# AnalogIn_Teensy_V05.net
KiCad netlist of a schematic drawn in EAGLE
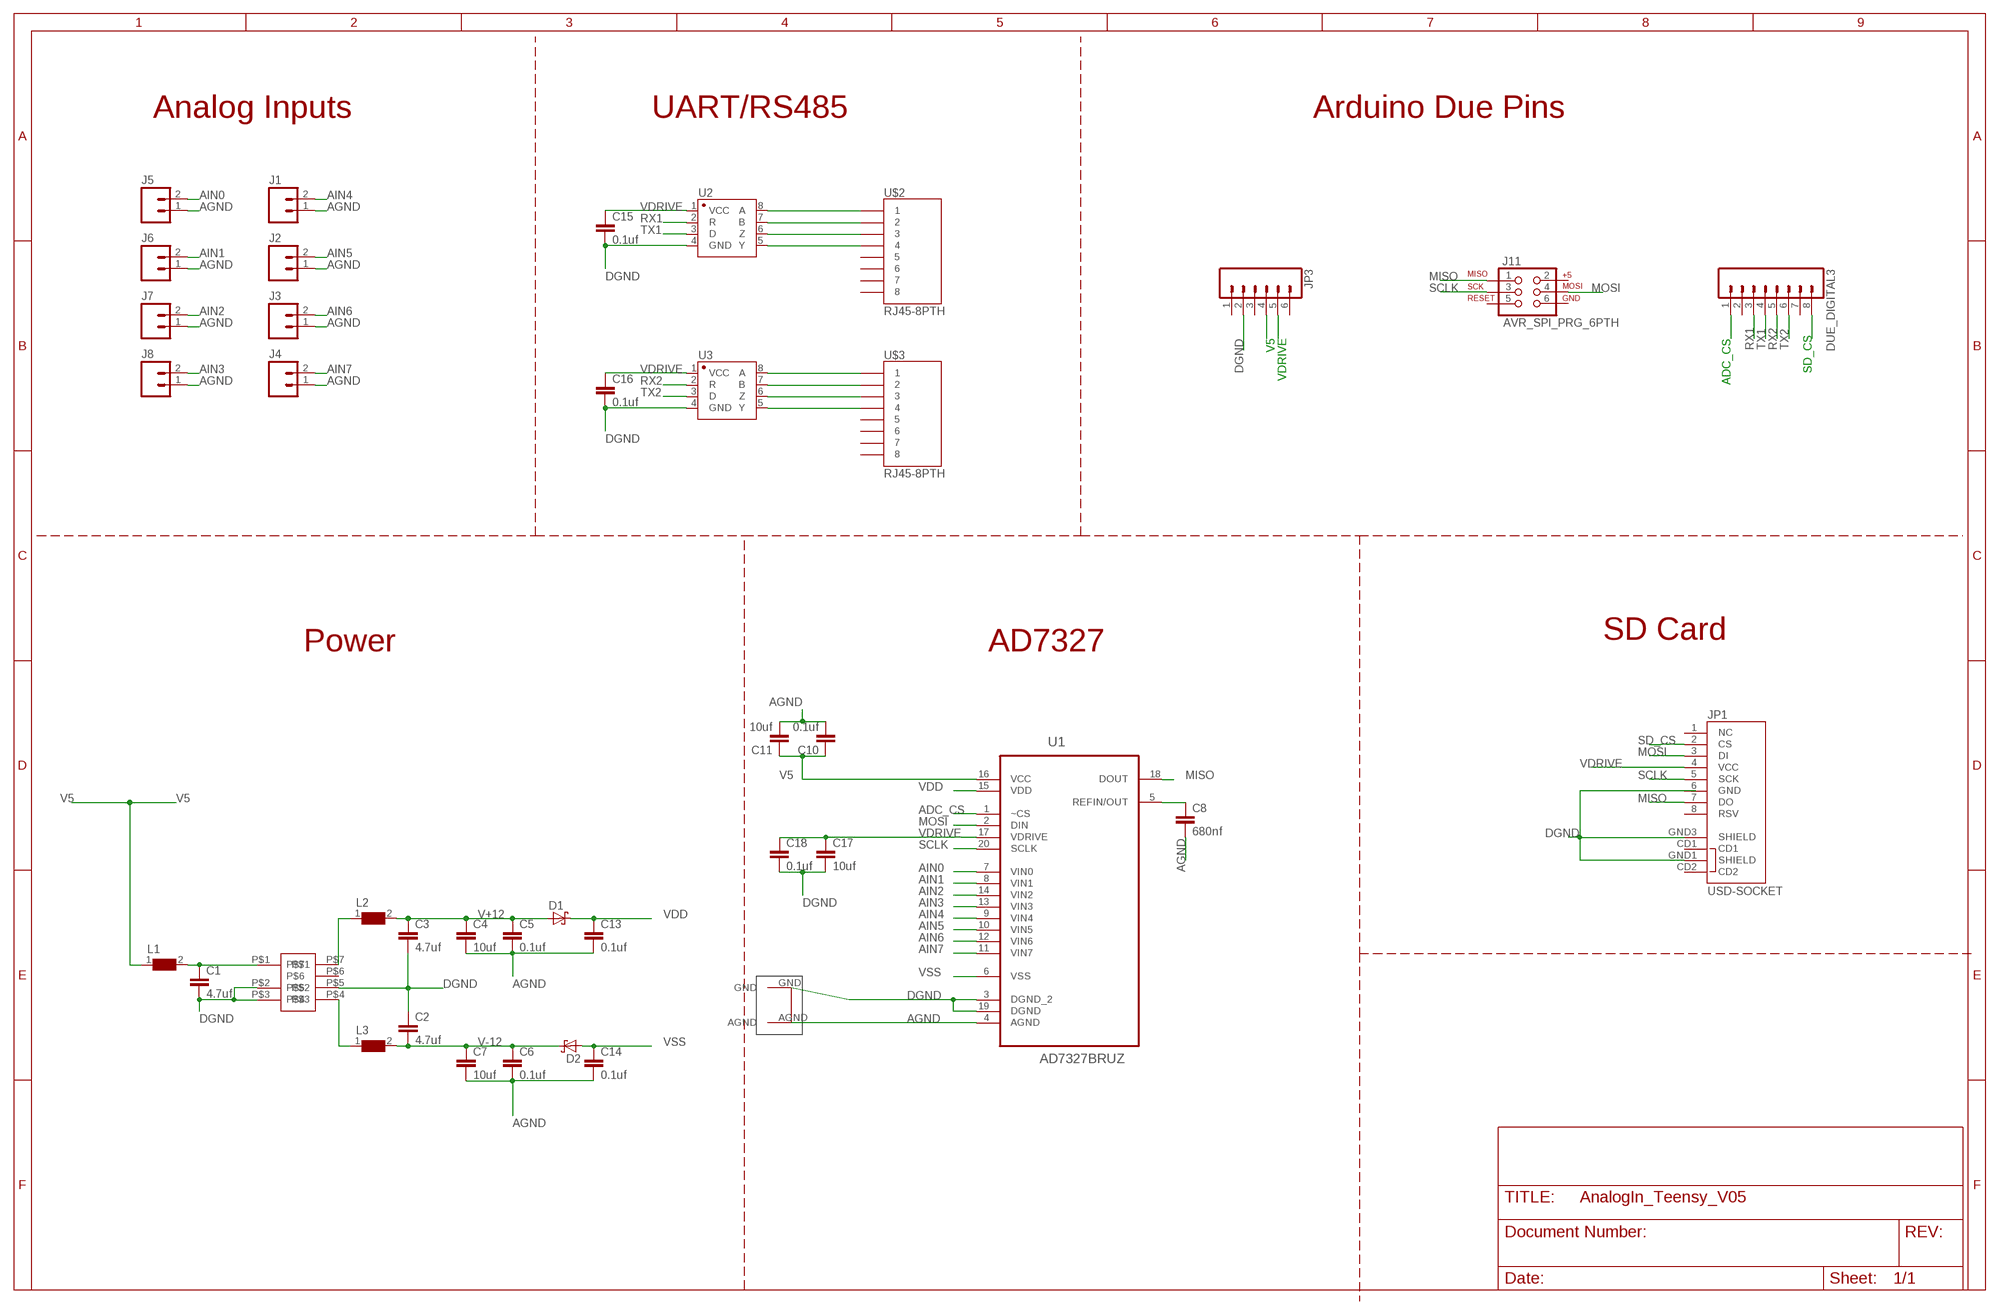
[diagram p0: schematic, sheet 1]

(export (version "E")
  (design (tool "Eeschema 10.0.6"))
  (components
    (comp (ref "C1")
      (value "4.7uf")
      (footprint "eagle-import:1206")
      (libsource (lib "eagle-import") (part "CAP1206"))
    )
    (comp (ref "C2")
      (value "4.7uf")
      (footprint "eagle-import:1206")
      (libsource (lib "eagle-import") (part "CAP1206"))
    )
    (comp (ref "C3")
      (value "4.7uf")
      (footprint "eagle-import:1206")
      (libsource (lib "eagle-import") (part "CAP1206"))
    )
    (comp (ref "C4")
      (value "10uf")
      (footprint "eagle-import:1206")
      (libsource (lib "eagle-import") (part "CAP1206"))
    )
    (comp (ref "C5")
      (value "0.1uf")
      (footprint "eagle-import:1206")
      (libsource (lib "eagle-import") (part "CAP1206"))
    )
    (comp (ref "C6")
      (value "0.1uf")
      (footprint "eagle-import:1206")
      (libsource (lib "eagle-import") (part "CAP1206"))
    )
    (comp (ref "C7")
      (value "10uf")
      (footprint "eagle-import:1206")
      (libsource (lib "eagle-import") (part "CAP1206"))
    )
    (comp (ref "C8")
      (value "680nf")
      (footprint "eagle-import:1206")
      (libsource (lib "eagle-import") (part "CAP1206"))
    )
    (comp (ref "C10")
      (value "0.1uf")
      (footprint "eagle-import:0603-CAP")
      (libsource (lib "eagle-import") (part "CAP0603-CAP"))
    )
    (comp (ref "C11")
      (value "10uf")
      (footprint "eagle-import:0603-CAP")
      (libsource (lib "eagle-import") (part "CAP0603-CAP"))
    )
    (comp (ref "C13")
      (value "0.1uf")
      (footprint "eagle-import:1206")
      (libsource (lib "eagle-import") (part "CAP1206"))
    )
    (comp (ref "C14")
      (value "0.1uf")
      (footprint "eagle-import:1206")
      (libsource (lib "eagle-import") (part "CAP1206"))
    )
    (comp (ref "C15")
      (value "0.1uf")
      (footprint "eagle-import:0603-CAP")
      (libsource (lib "eagle-import") (part "CAP0603-CAP"))
    )
    (comp (ref "C16")
      (value "0.1uf")
      (footprint "eagle-import:0603-CAP")
      (libsource (lib "eagle-import") (part "CAP0603-CAP"))
    )
    (comp (ref "C17")
      (value "10uf")
      (footprint "eagle-import:0603-CAP")
      (libsource (lib "eagle-import") (part "CAP0603-CAP"))
    )
    (comp (ref "C18")
      (value "0.1uf")
      (footprint "eagle-import:0603-CAP")
      (libsource (lib "eagle-import") (part "CAP0603-CAP"))
    )
    (comp (ref "D1")
      (value "SCHOTTKY-DIODESMD")
      (footprint "eagle-import:SMB")
      (libsource (lib "eagle-import") (part "SCHOTTKY-DIODESMD"))
    )
    (comp (ref "D2")
      (value "SCHOTTKY-DIODESMD")
      (footprint "eagle-import:SMB")
      (libsource (lib "eagle-import") (part "SCHOTTKY-DIODESMD"))
    )
    (comp (ref "DUE_DIGITAL3")
      (value "M081X08")
      (footprint "eagle-import:1X08")
      (libsource (lib "eagle-import") (part "M081X08"))
    )
    (comp (ref "J1")
      (value "M023.5MM")
      (footprint "eagle-import:SCREWTERMINAL-3.5MM-2")
      (libsource (lib "eagle-import") (part "M023.5MM"))
    )
    (comp (ref "J2")
      (value "M023.5MM")
      (footprint "eagle-import:SCREWTERMINAL-3.5MM-2")
      (libsource (lib "eagle-import") (part "M023.5MM"))
    )
    (comp (ref "J3")
      (value "M023.5MM")
      (footprint "eagle-import:SCREWTERMINAL-3.5MM-2")
      (libsource (lib "eagle-import") (part "M023.5MM"))
    )
    (comp (ref "J4")
      (value "M023.5MM")
      (footprint "eagle-import:SCREWTERMINAL-3.5MM-2")
      (libsource (lib "eagle-import") (part "M023.5MM"))
    )
    (comp (ref "J5")
      (value "M023.5MM")
      (footprint "eagle-import:SCREWTERMINAL-3.5MM-2")
      (libsource (lib "eagle-import") (part "M023.5MM"))
    )
    (comp (ref "J6")
      (value "M023.5MM")
      (footprint "eagle-import:SCREWTERMINAL-3.5MM-2")
      (libsource (lib "eagle-import") (part "M023.5MM"))
    )
    (comp (ref "J7")
      (value "M023.5MM")
      (footprint "eagle-import:SCREWTERMINAL-3.5MM-2")
      (libsource (lib "eagle-import") (part "M023.5MM"))
    )
    (comp (ref "J8")
      (value "M023.5MM")
      (footprint "eagle-import:SCREWTERMINAL-3.5MM-2")
      (libsource (lib "eagle-import") (part "M023.5MM"))
    )
    (comp (ref "J11")
      (value "AVR_SPI_PRG_6PTH")
      (footprint "eagle-import:2X3")
      (libsource (lib "eagle-import") (part "AVR_SPI_PRG_6PTH"))
    )
    (comp (ref "JP1")
      (value "USD-SOCKET")
      (footprint "eagle-import:MICROSD_1_1")
      (libsource (lib "eagle-import") (part "USD-SOCKET"))
    )
    (comp (ref "JP3")
      (value "M06SILK_FEMALE_PTH")
      (footprint "eagle-import:1X06")
      (libsource (lib "eagle-import") (part "M06SILK_FEMALE_PTH"))
    )
    (comp (ref "L1")
      (value "WE-CBF-742792118_1206")
      (footprint "eagle-import:1206")
      (fields (field (name "MPN") "742792118"))
      (libsource (lib "eagle-import") (part "WE-CBF_1206-742792118"))
    )
    (comp (ref "L2")
      (value "WE-CBF-742792118_1206")
      (footprint "eagle-import:1206")
      (fields (field (name "MPN") "742792118"))
      (libsource (lib "eagle-import") (part "WE-CBF_1206-742792118"))
    )
    (comp (ref "L3")
      (value "WE-CBF-742792118_1206")
      (footprint "eagle-import:1206")
      (fields (field (name "MPN") "742792118"))
      (libsource (lib "eagle-import") (part "WE-CBF_1206-742792118"))
    )
    (comp (ref "U$1")
      (value "TDK_LAMBDA_5_TO_BI_12_125MA")
      (footprint "eagle-import:TDK_LAMBDA_5_TO_BI_12_125MA")
      (libsource (lib "eagle-import") (part "TDK_LAMBDA_5_TO_BI_12_125MA"))
    )
    (comp (ref "U$2")
      (value "RJ45-8PTH")
      (footprint "eagle-import:RJ45-8")
      (libsource (lib "eagle-import") (part "RJ45-8PTH"))
    )
    (comp (ref "U$3")
      (value "RJ45-8PTH")
      (footprint "eagle-import:RJ45-8")
      (libsource (lib "eagle-import") (part "RJ45-8PTH"))
    )
    (comp (ref "U$4")
      (value "GNDPLANESHRT")
      (footprint "eagle-import:GNDPLANESHRT")
      (libsource (lib "eagle-import") (part "GNDPLANESHRT"))
    )
    (comp (ref "U1")
      (value "AD7327BRUZ")
      (footprint "eagle-import:SOP65P640X120-20N")
      (libsource (lib "eagle-import") (part "AD7327BRUZ"))
    )
    (comp (ref "U2")
      (value "SN65HVD31DR")
      (footprint "eagle-import:SO08")
      (libsource (lib "eagle-import") (part "SN65HVD31DR"))
    )
    (comp (ref "U3")
      (value "SN65HVD31DR")
      (footprint "eagle-import:SO08")
      (libsource (lib "eagle-import") (part "SN65HVD31DR"))
    )
  )
  (nets
    (net (code "1") (name "/ADC_CS") (class "Default")
      (node (ref "DUE_DIGITAL3") (pin "1") (pinfunction "1_1") (pintype "passive"))
      (node (ref "U1") (pin "1") (pinfunction "~{CS}_1") (pintype "input"))
    )
    (net (code "2") (name "/AGND") (class "Default")
      (node (ref "C10") (pin "2") (pinfunction "2_2") (pintype "passive"))
      (node (ref "C11") (pin "2") (pinfunction "2_2") (pintype "passive"))
      (node (ref "C13") (pin "2") (pinfunction "2_2") (pintype "passive"))
      (node (ref "C14") (pin "2") (pinfunction "2_2") (pintype "passive"))
      (node (ref "C4") (pin "2") (pinfunction "2_2") (pintype "passive"))
      (node (ref "C5") (pin "2") (pinfunction "2_2") (pintype "passive"))
      (node (ref "C6") (pin "2") (pinfunction "2_2") (pintype "passive"))
      (node (ref "C7") (pin "2") (pinfunction "2_2") (pintype "passive"))
      (node (ref "C8") (pin "2") (pinfunction "2_2") (pintype "passive"))
      (node (ref "J1") (pin "1") (pinfunction "1_1") (pintype "passive"))
      (node (ref "J2") (pin "1") (pinfunction "1_1") (pintype "passive"))
      (node (ref "J3") (pin "1") (pinfunction "1_1") (pintype "passive"))
      (node (ref "J4") (pin "1") (pinfunction "1_1") (pintype "passive"))
      (node (ref "J5") (pin "1") (pinfunction "1_1") (pintype "passive"))
      (node (ref "J6") (pin "1") (pinfunction "1_1") (pintype "passive"))
      (node (ref "J7") (pin "1") (pinfunction "1_1") (pintype "passive"))
      (node (ref "J8") (pin "1") (pinfunction "1_1") (pintype "passive"))
      (node (ref "U$4") (pin "AGND") (pinfunction "AGND_AGND") (pintype "bidirectional"))
      (node (ref "U1") (pin "4") (pinfunction "AGND_4") (pintype "passive"))
    )
    (net (code "3") (name "/AIN0") (class "Default")
      (node (ref "J5") (pin "2") (pinfunction "2_2") (pintype "passive"))
      (node (ref "U1") (pin "7") (pinfunction "VIN0_7") (pintype "input"))
    )
    (net (code "4") (name "/AIN1") (class "Default")
      (node (ref "J6") (pin "2") (pinfunction "2_2") (pintype "passive"))
      (node (ref "U1") (pin "8") (pinfunction "VIN1_8") (pintype "input"))
    )
    (net (code "5") (name "/AIN2") (class "Default")
      (node (ref "J7") (pin "2") (pinfunction "2_2") (pintype "passive"))
      (node (ref "U1") (pin "14") (pinfunction "VIN2_14") (pintype "input"))
    )
    (net (code "6") (name "/AIN3") (class "Default")
      (node (ref "J8") (pin "2") (pinfunction "2_2") (pintype "passive"))
      (node (ref "U1") (pin "13") (pinfunction "VIN3_13") (pintype "input"))
    )
    (net (code "7") (name "/AIN4") (class "Default")
      (node (ref "J1") (pin "2") (pinfunction "2_2") (pintype "passive"))
      (node (ref "U1") (pin "9") (pinfunction "VIN4_9") (pintype "input"))
    )
    (net (code "8") (name "/AIN5") (class "Default")
      (node (ref "J2") (pin "2") (pinfunction "2_2") (pintype "passive"))
      (node (ref "U1") (pin "10") (pinfunction "VIN5_10") (pintype "input"))
    )
    (net (code "9") (name "/AIN6") (class "Default")
      (node (ref "J3") (pin "2") (pinfunction "2_2") (pintype "passive"))
      (node (ref "U1") (pin "12") (pinfunction "VIN6_12") (pintype "input"))
    )
    (net (code "10") (name "/AIN7") (class "Default")
      (node (ref "J4") (pin "2") (pinfunction "2_2") (pintype "passive"))
      (node (ref "U1") (pin "11") (pinfunction "VIN7_11") (pintype "input"))
    )
    (net (code "11") (name "/DGND") (class "Default")
      (node (ref "C1") (pin "2") (pinfunction "2_2") (pintype "passive"))
      (node (ref "C15") (pin "2") (pinfunction "2_2") (pintype "passive"))
      (node (ref "C16") (pin "2") (pinfunction "2_2") (pintype "passive"))
      (node (ref "C17") (pin "2") (pinfunction "2_2") (pintype "passive"))
      (node (ref "C18") (pin "2") (pinfunction "2_2") (pintype "passive"))
      (node (ref "C2") (pin "1") (pinfunction "1_1") (pintype "passive"))
      (node (ref "C3") (pin "2") (pinfunction "2_2") (pintype "passive"))
      (node (ref "JP1") (pin "GND1") (pinfunction "SHIELD_GND1") (pintype "bidirectional"))
      (node (ref "JP1") (pin "GND3") (pinfunction "SHIELD_GND3") (pintype "bidirectional"))
      (node (ref "JP3") (pin "2") (pinfunction "2_2") (pintype "passive"))
      (node (ref "U$1") (pin "P$2") (pinfunction "P$2_P$2") (pintype "bidirectional"))
      (node (ref "U$1") (pin "P$3") (pinfunction "P$3_P$3") (pintype "bidirectional"))
      (node (ref "U$1") (pin "P$5") (pinfunction "P$5_P$5") (pintype "bidirectional"))
      (node (ref "U$4") (pin "GND") (pinfunction "GND_GND") (pintype "bidirectional"))
      (node (ref "U1") (pin "19") (pinfunction "DGND_19") (pintype "passive"))
      (node (ref "U1") (pin "3") (pinfunction "DGND_2_3") (pintype "passive"))
      (node (ref "U2") (pin "4") (pinfunction "GND_4") (pintype "bidirectional"))
      (node (ref "U3") (pin "4") (pinfunction "GND_4") (pintype "bidirectional"))
    )
    (net (code "12") (name "/MISO") (class "Default")
      (node (ref "J11") (pin "1") (pinfunction "1_1") (pintype "passive"))
      (node (ref "JP1") (pin "7") (pinfunction "DO_7") (pintype "bidirectional"))
      (node (ref "U1") (pin "18") (pinfunction "DOUT_18") (pintype "output"))
    )
    (net (code "13") (name "/MOSI") (class "Default")
      (node (ref "J11") (pin "4") (pinfunction "4_4") (pintype "passive"))
      (node (ref "JP1") (pin "3") (pinfunction "DI_3") (pintype "bidirectional"))
      (node (ref "U1") (pin "2") (pinfunction "DIN_2") (pintype "input"))
    )
    (net (code "14") (name "/RX1") (class "Default")
      (node (ref "DUE_DIGITAL3") (pin "3") (pinfunction "3_3") (pintype "passive"))
      (node (ref "U2") (pin "2") (pinfunction "R_2") (pintype "bidirectional"))
    )
    (net (code "15") (name "/RX2") (class "Default")
      (node (ref "DUE_DIGITAL3") (pin "5") (pinfunction "5_5") (pintype "passive"))
      (node (ref "U3") (pin "2") (pinfunction "R_2") (pintype "bidirectional"))
    )
    (net (code "16") (name "/SCLK") (class "Default")
      (node (ref "J11") (pin "3") (pinfunction "3_3") (pintype "passive"))
      (node (ref "JP1") (pin "5") (pinfunction "SCK_5") (pintype "bidirectional"))
      (node (ref "U1") (pin "20") (pinfunction "SCLK_20") (pintype "input"))
    )
    (net (code "17") (name "/SD_CS") (class "Default")
      (node (ref "DUE_DIGITAL3") (pin "8") (pinfunction "8_8") (pintype "passive"))
      (node (ref "JP1") (pin "2") (pinfunction "CS_2") (pintype "bidirectional"))
    )
    (net (code "18") (name "/TX1") (class "Default")
      (node (ref "DUE_DIGITAL3") (pin "4") (pinfunction "4_4") (pintype "passive"))
      (node (ref "U2") (pin "3") (pinfunction "D_3") (pintype "bidirectional"))
    )
    (net (code "19") (name "/TX2") (class "Default")
      (node (ref "DUE_DIGITAL3") (pin "6") (pinfunction "6_6") (pintype "passive"))
      (node (ref "U3") (pin "3") (pinfunction "D_3") (pintype "bidirectional"))
    )
    (net (code "20") (name "/V+12") (class "Default")
      (node (ref "C3") (pin "1") (pinfunction "1_1") (pintype "passive"))
      (node (ref "C4") (pin "1") (pinfunction "1_1") (pintype "passive"))
      (node (ref "C5") (pin "1") (pinfunction "1_1") (pintype "passive"))
      (node (ref "D1") (pin "A") (pinfunction "A_A") (pintype "passive"))
      (node (ref "L2") (pin "2") (pinfunction "2_2") (pintype "passive"))
    )
    (net (code "21") (name "/V-12") (class "Default")
      (node (ref "C2") (pin "2") (pinfunction "2_2") (pintype "passive"))
      (node (ref "C6") (pin "1") (pinfunction "1_1") (pintype "passive"))
      (node (ref "C7") (pin "1") (pinfunction "1_1") (pintype "passive"))
      (node (ref "D2") (pin "C") (pinfunction "C_C") (pintype "passive"))
      (node (ref "L3") (pin "2") (pinfunction "2_2") (pintype "passive"))
    )
    (net (code "22") (name "/V5") (class "Default")
      (node (ref "C10") (pin "1") (pinfunction "1_1") (pintype "passive"))
      (node (ref "C11") (pin "1") (pinfunction "1_1") (pintype "passive"))
      (node (ref "JP3") (pin "4") (pinfunction "4_4") (pintype "passive"))
      (node (ref "L1") (pin "1") (pinfunction "1_1") (pintype "passive"))
      (node (ref "U1") (pin "16") (pinfunction "VCC_16") (pintype "power_in"))
    )
    (net (code "23") (name "/VDD") (class "Default")
      (node (ref "C13") (pin "1") (pinfunction "1_1") (pintype "passive"))
      (node (ref "D1") (pin "C") (pinfunction "C_C") (pintype "passive"))
      (node (ref "U1") (pin "15") (pinfunction "VDD_15") (pintype "power_in"))
    )
    (net (code "24") (name "/VDRIVE") (class "Default")
      (node (ref "C15") (pin "1") (pinfunction "1_1") (pintype "passive"))
      (node (ref "C16") (pin "1") (pinfunction "1_1") (pintype "passive"))
      (node (ref "C17") (pin "1") (pinfunction "1_1") (pintype "passive"))
      (node (ref "C18") (pin "1") (pinfunction "1_1") (pintype "passive"))
      (node (ref "JP1") (pin "4") (pinfunction "VCC_4") (pintype "bidirectional"))
      (node (ref "JP3") (pin "5") (pinfunction "5_5") (pintype "passive"))
      (node (ref "U1") (pin "17") (pinfunction "VDRIVE_17") (pintype "input"))
      (node (ref "U2") (pin "1") (pinfunction "VCC_1") (pintype "bidirectional"))
      (node (ref "U3") (pin "1") (pinfunction "VCC_1") (pintype "bidirectional"))
    )
    (net (code "25") (name "/VSS") (class "Default")
      (node (ref "C14") (pin "1") (pinfunction "1_1") (pintype "passive"))
      (node (ref "D2") (pin "A") (pinfunction "A_A") (pintype "passive"))
      (node (ref "U1") (pin "6") (pinfunction "VSS_6") (pintype "power_in"))
    )
    (net (code "26") (name "Net-(C1-Pad1)") (class "Default")
      (node (ref "C1") (pin "1") (pinfunction "1_1") (pintype "passive"))
      (node (ref "L1") (pin "2") (pinfunction "2_2") (pintype "passive"))
      (node (ref "U$1") (pin "P$1") (pinfunction "P$1_P$1") (pintype "bidirectional"))
    )
    (net (code "27") (name "Net-(L2-Pad1)") (class "Default")
      (node (ref "L2") (pin "1") (pinfunction "1_1") (pintype "passive"))
      (node (ref "U$1") (pin "P$7") (pinfunction "P$7_P$7") (pintype "bidirectional"))
    )
    (net (code "28") (name "Net-(L3-Pad1)") (class "Default")
      (node (ref "L3") (pin "1") (pinfunction "1_1") (pintype "passive"))
      (node (ref "U$1") (pin "P$4") (pinfunction "P$4_P$4") (pintype "bidirectional"))
    )
    (net (code "29") (name "Net-(U1-REFIN{slash}OUT)") (class "Default")
      (node (ref "C8") (pin "1") (pinfunction "1_1") (pintype "passive"))
      (node (ref "U1") (pin "5") (pinfunction "REFIN/OUT_5") (pintype "bidirectional"))
    )
    (net (code "30") (name "Net-(U2-A)") (class "Default")
      (node (ref "U$2") (pin "1") (pinfunction "1_1") (pintype "bidirectional"))
      (node (ref "U2") (pin "8") (pinfunction "A_8") (pintype "bidirectional"))
    )
    (net (code "31") (name "Net-(U2-B)") (class "Default")
      (node (ref "U$2") (pin "2") (pinfunction "2_2") (pintype "bidirectional"))
      (node (ref "U2") (pin "7") (pinfunction "B_7") (pintype "bidirectional"))
    )
    (net (code "32") (name "Net-(U2-Y)") (class "Default")
      (node (ref "U$2") (pin "4") (pinfunction "4_4") (pintype "bidirectional"))
      (node (ref "U2") (pin "5") (pinfunction "Y_5") (pintype "bidirectional"))
    )
    (net (code "33") (name "Net-(U2-Z)") (class "Default")
      (node (ref "U$2") (pin "3") (pinfunction "3_3") (pintype "bidirectional"))
      (node (ref "U2") (pin "6") (pinfunction "Z_6") (pintype "bidirectional"))
    )
    (net (code "34") (name "Net-(U3-A)") (class "Default")
      (node (ref "U$3") (pin "1") (pinfunction "1_1") (pintype "bidirectional"))
      (node (ref "U3") (pin "8") (pinfunction "A_8") (pintype "bidirectional"))
    )
    (net (code "35") (name "Net-(U3-B)") (class "Default")
      (node (ref "U$3") (pin "2") (pinfunction "2_2") (pintype "bidirectional"))
      (node (ref "U3") (pin "7") (pinfunction "B_7") (pintype "bidirectional"))
    )
    (net (code "36") (name "Net-(U3-Y)") (class "Default")
      (node (ref "U$3") (pin "4") (pinfunction "4_4") (pintype "bidirectional"))
      (node (ref "U3") (pin "5") (pinfunction "Y_5") (pintype "bidirectional"))
    )
    (net (code "37") (name "Net-(U3-Z)") (class "Default")
      (node (ref "U$3") (pin "3") (pinfunction "3_3") (pintype "bidirectional"))
      (node (ref "U3") (pin "6") (pinfunction "Z_6") (pintype "bidirectional"))
    )
    (net (code "38") (name "unconnected-(DUE_DIGITAL3-Pad2)") (class "Default")
      (node (ref "DUE_DIGITAL3") (pin "2") (pinfunction "2_2") (pintype "passive"))
    )
    (net (code "39") (name "unconnected-(DUE_DIGITAL3-Pad7)") (class "Default")
      (node (ref "DUE_DIGITAL3") (pin "7") (pinfunction "7_7") (pintype "passive"))
    )
    (net (code "40") (name "unconnected-(J11-Pad2)") (class "Default")
      (node (ref "J11") (pin "2") (pinfunction "2_2") (pintype "passive"))
    )
    (net (code "41") (name "unconnected-(J11-Pad5)") (class "Default")
      (node (ref "J11") (pin "5") (pinfunction "5_5") (pintype "passive"))
    )
    (net (code "42") (name "unconnected-(J11-Pad6)") (class "Default")
      (node (ref "J11") (pin "6") (pinfunction "6_6") (pintype "passive"))
    )
    (net (code "43") (name "unconnected-(JP1-GND-Pad6)") (class "Default")
      (node (ref "JP1") (pin "6") (pinfunction "GND_6") (pintype "bidirectional"))
    )
    (net (code "44") (name "unconnected-(JP1-NC-Pad1)") (class "Default")
      (node (ref "JP1") (pin "1") (pinfunction "NC_1") (pintype "bidirectional"))
    )
    (net (code "45") (name "unconnected-(JP1-PadCD1)") (class "Default")
      (node (ref "JP1") (pin "CD1") (pinfunction "CD1_CD1") (pintype "bidirectional"))
    )
    (net (code "46") (name "unconnected-(JP1-PadCD2)") (class "Default")
      (node (ref "JP1") (pin "CD2") (pinfunction "CD2_CD2") (pintype "bidirectional"))
    )
    (net (code "47") (name "unconnected-(JP1-RSV-Pad8)") (class "Default")
      (node (ref "JP1") (pin "8") (pinfunction "RSV_8") (pintype "bidirectional"))
    )
    (net (code "48") (name "unconnected-(JP3-Pad1)") (class "Default")
      (node (ref "JP3") (pin "1") (pinfunction "1_1") (pintype "passive"))
    )
    (net (code "49") (name "unconnected-(JP3-Pad3)") (class "Default")
      (node (ref "JP3") (pin "3") (pinfunction "3_3") (pintype "passive"))
    )
    (net (code "50") (name "unconnected-(JP3-Pad6)") (class "Default")
      (node (ref "JP3") (pin "6") (pinfunction "6_6") (pintype "passive"))
    )
    (net (code "51") (name "unconnected-(U$1-PadP$6)") (class "Default")
      (node (ref "U$1") (pin "P$6") (pinfunction "P$6_P$6") (pintype "bidirectional"))
    )
    (net (code "52") (name "unconnected-(U$2-Pad5)") (class "Default")
      (node (ref "U$2") (pin "5") (pinfunction "5_5") (pintype "bidirectional"))
    )
    (net (code "53") (name "unconnected-(U$2-Pad6)") (class "Default")
      (node (ref "U$2") (pin "6") (pinfunction "6_6") (pintype "bidirectional"))
    )
    (net (code "54") (name "unconnected-(U$2-Pad7)") (class "Default")
      (node (ref "U$2") (pin "7") (pinfunction "7_7") (pintype "bidirectional"))
    )
    (net (code "55") (name "unconnected-(U$2-Pad8)") (class "Default")
      (node (ref "U$2") (pin "8") (pinfunction "8_8") (pintype "bidirectional"))
    )
    (net (code "56") (name "unconnected-(U$3-Pad5)") (class "Default")
      (node (ref "U$3") (pin "5") (pinfunction "5_5") (pintype "bidirectional"))
    )
    (net (code "57") (name "unconnected-(U$3-Pad6)") (class "Default")
      (node (ref "U$3") (pin "6") (pinfunction "6_6") (pintype "bidirectional"))
    )
    (net (code "58") (name "unconnected-(U$3-Pad7)") (class "Default")
      (node (ref "U$3") (pin "7") (pinfunction "7_7") (pintype "bidirectional"))
    )
    (net (code "59") (name "unconnected-(U$3-Pad8)") (class "Default")
      (node (ref "U$3") (pin "8") (pinfunction "8_8") (pintype "bidirectional"))
    )
  )
)
